# Port.net
KiCad netlist of a schematic drawn in Altium Designer
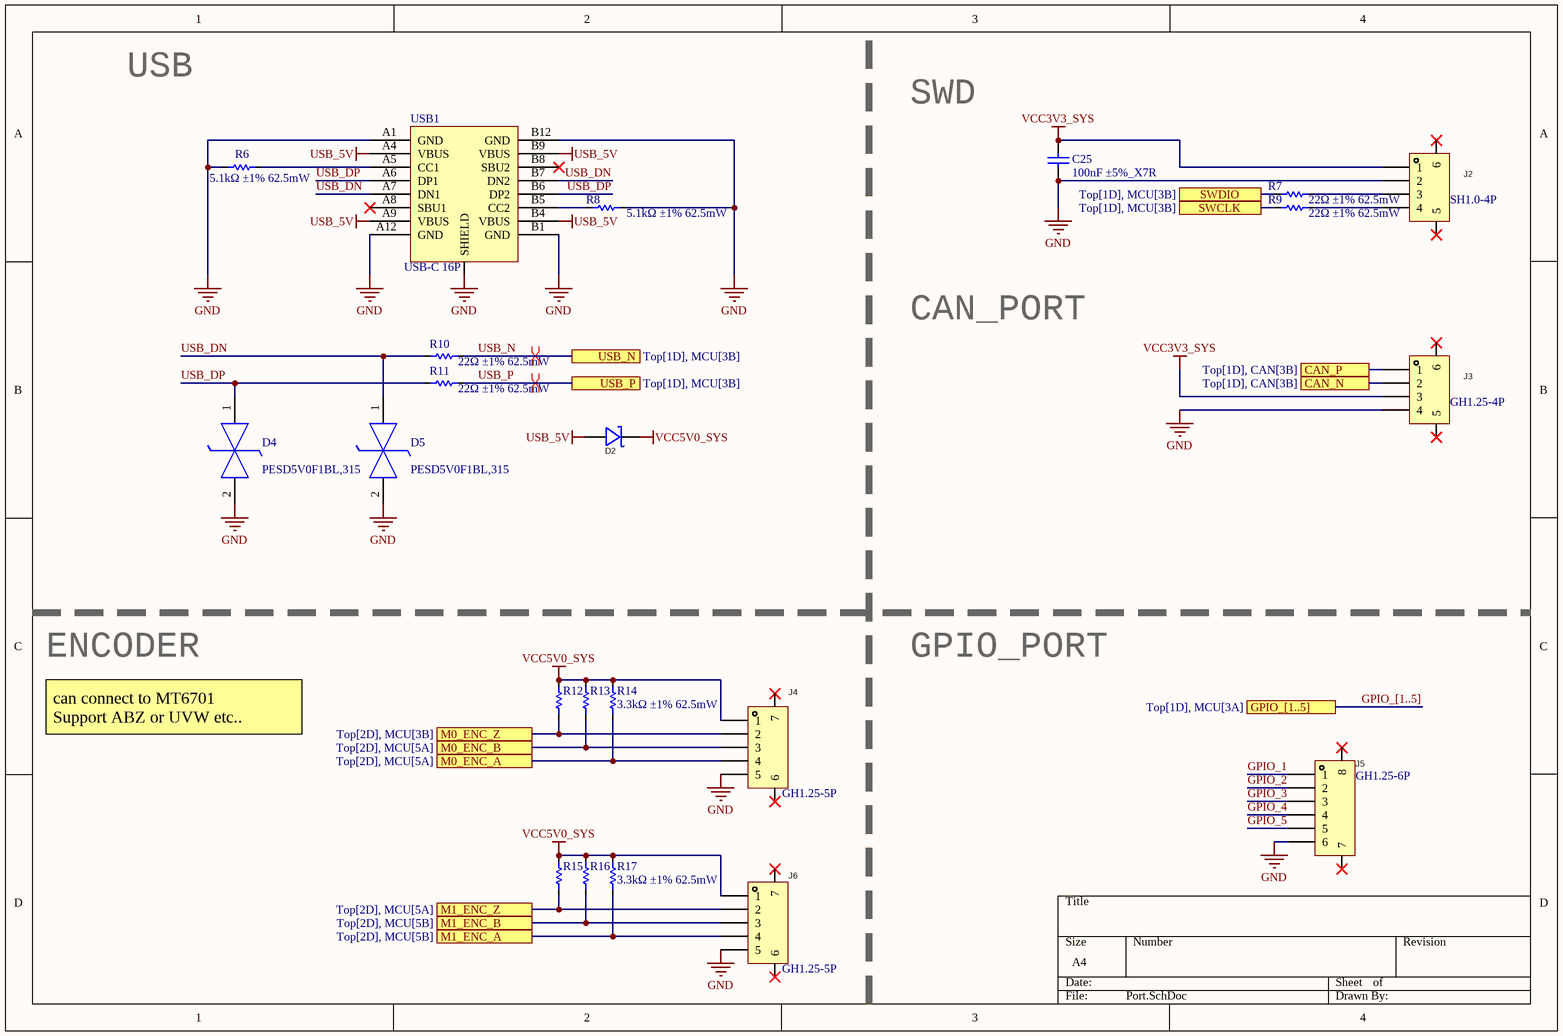
[diagram p0: Port.SchDoc]

(export (version "E")
  (design (tool "Eeschema 10.0.6"))
  (components
    (comp (ref "C25")
      (value "100nF ±5%_X7R")
      (footprint "C0402")
      (description "Capacitor")
      (fields (field (name "PUBLISHER") "Altium Limited"))
      (libsource (lib "Component") (part "Cap"))
    )
    (comp (ref "D2")
      (value "B340A-13-F")
      (footprint "SMA_L4.4-W2.6-LS5.0-RD")
      (description "直流反向耐压(Vr):40V;平均整流电流(Io):3A;正向压降(Vf):500mV@3A;")
      (fields (field (name "MANUFACTURER") "DIODES(美台)"))
      (libsource (lib "Component") (part "Diode_Schottky"))
    )
    (comp (ref "D4")
      (value "PESD5V0F1BL,315")
      (footprint "SamacSys:PESD5V0S1BL315")
      (description "Diode ESD (Bi-directional)")
      (fields (field (name "MOUSER PART NUMBER") "771-PESD5V0F1BL315"))
      (libsource (lib "*") (part "PESD5V0F1BL,315"))
    )
    (comp (ref "D5")
      (value "PESD5V0F1BL,315")
      (footprint "SamacSys:PESD5V0S1BL315")
      (description "Diode ESD (Bi-directional)")
      (fields (field (name "MOUSER PART NUMBER") "771-PESD5V0F1BL315"))
      (libsource (lib "*") (part "PESD5V0F1BL,315"))
    )
    (comp (ref "J2")
      (value "SH1.0-4P")
      (footprint "CONN-SMD_4P-P1.00_BX-SH1.0-4PWT")
      (description "CONN-SMD_4P-P1.25_532610571-2")
      (fields
        (field (name "MANUFACTURER") "BOOMELE(博穆精密)")
        (field (name "MANUFACTURER PART") "GH1.25-5PLTPZ")
      )
      (libsource (lib "Connectivity_Plugs") (part "SH1.0-4P"))
    )
    (comp (ref "J3")
      (value "GH1.25-4P")
      (footprint "GH1.25-4P")
      (fields
        (field (name "MANUFACTURER") "BOOMELE(博穆精密)")
        (field (name "MANUFACTURER PART") "GH1.25-5PLTPZ")
      )
      (libsource (lib "Connectivity_Plugs") (part "GH1.25-4P"))
    )
    (comp (ref "J4")
      (value "GH1.25-5P")
      (footprint "GH1.25-5P")
      (fields
        (field (name "MANUFACTURER") "BOOMELE(博穆精密)")
        (field (name "MANUFACTURER PART") "GH1.25-5PLTPZ")
      )
      (libsource (lib "Connectivity_Plugs") (part "GH1.25-5P"))
    )
    (comp (ref "J5")
      (value "GH1.25-6P")
      (footprint "GH1.25-6P")
      (fields
        (field (name "MANUFACTURER") "BOOMELE(博穆精密)")
        (field (name "MANUFACTURER PART") "GH1.25-5PLTPZ")
      )
      (libsource (lib "Connectivity_Plugs") (part "GH1.25-6P"))
    )
    (comp (ref "J6")
      (value "GH1.25-5P")
      (footprint "GH1.25-5P")
      (fields
        (field (name "MANUFACTURER") "BOOMELE(博穆精密)")
        (field (name "MANUFACTURER PART") "GH1.25-5PLTPZ")
      )
      (libsource (lib "Connectivity_Plugs") (part "GH1.25-5P"))
    )
    (comp (ref "R6")
      (value "5.1kΩ ±1% 62.5mW")
      (footprint "R0402")
      (description "Resistor")
      (fields (field (name "PUBLISHER") "Altium Limited"))
      (libsource (lib "Component") (part "Res"))
    )
    (comp (ref "R7")
      (value "22Ω ±1% 62.5mW")
      (footprint "R0402")
      (description "Resistor")
      (fields (field (name "PUBLISHER") "Altium Limited"))
      (libsource (lib "Component") (part "Res"))
    )
    (comp (ref "R8")
      (value "5.1kΩ ±1% 62.5mW")
      (footprint "R0402")
      (description "Resistor")
      (fields (field (name "PUBLISHER") "Altium Limited"))
      (libsource (lib "Component") (part "Res"))
    )
    (comp (ref "R9")
      (value "22Ω ±1% 62.5mW")
      (footprint "R0402")
      (description "Resistor")
      (fields (field (name "PUBLISHER") "Altium Limited"))
      (libsource (lib "Component") (part "Res"))
    )
    (comp (ref "R10")
      (value "22Ω ±1% 62.5mW")
      (footprint "R0402")
      (description "0402WGF220JTCE")
      (fields (field (name "PUBLISHER") "Altium Limited"))
      (libsource (lib "Component") (part "Res"))
    )
    (comp (ref "R11")
      (value "22Ω ±1% 62.5mW")
      (footprint "R0402")
      (description "0402WGF220JTCE")
      (fields (field (name "PUBLISHER") "Altium Limited"))
      (libsource (lib "Component") (part "Res"))
    )
    (comp (ref "R12")
      (value "3.3kΩ ±1% 62.5mW")
      (footprint "R0402")
      (fields (field (name "PUBLISHER") "Altium Limited"))
      (libsource (lib "Component") (part "Res"))
    )
    (comp (ref "R13")
      (value "3.3kΩ ±1% 62.5mW")
      (footprint "R0402")
      (fields (field (name "PUBLISHER") "Altium Limited"))
      (libsource (lib "Component") (part "Res"))
    )
    (comp (ref "R14")
      (value "3.3kΩ ±1% 62.5mW")
      (footprint "R0402")
      (fields (field (name "PUBLISHER") "Altium Limited"))
      (libsource (lib "Component") (part "Res"))
    )
    (comp (ref "R15")
      (value "3.3kΩ ±1% 62.5mW")
      (footprint "R0402")
      (fields (field (name "PUBLISHER") "Altium Limited"))
      (libsource (lib "Component") (part "Res"))
    )
    (comp (ref "R16")
      (value "3.3kΩ ±1% 62.5mW")
      (footprint "R0402")
      (fields (field (name "PUBLISHER") "Altium Limited"))
      (libsource (lib "Component") (part "Res"))
    )
    (comp (ref "R17")
      (value "3.3kΩ ±1% 62.5mW")
      (footprint "R0402")
      (fields (field (name "PUBLISHER") "Altium Limited"))
      (libsource (lib "Component") (part "Res"))
    )
    (comp (ref "USB1") (value "USB-C 16P") (footprint "USB-C-16P") (libsource (lib "USB") (part "USB-C 16P")))
  )
  (nets
    (net (code "1") (name "/CAN_N") (class "Default")
      (node (ref "J3") (pin "2") (pinfunction "2_2") (pintype "passive"))
    )
    (net (code "2") (name "/CAN_P") (class "Default")
      (node (ref "J3") (pin "1") (pinfunction "1_1") (pintype "passive"))
    )
    (net (code "3") (name "/GPIO_1") (class "Default")
      (node (ref "J5") (pin "1") (pinfunction "1_1") (pintype "passive"))
    )
    (net (code "4") (name "/GPIO_2") (class "Default")
      (node (ref "J5") (pin "2") (pinfunction "2_2") (pintype "passive"))
    )
    (net (code "5") (name "/GPIO_3") (class "Default")
      (node (ref "J5") (pin "3") (pinfunction "3_3") (pintype "passive"))
    )
    (net (code "6") (name "/GPIO_4") (class "Default")
      (node (ref "J5") (pin "4") (pinfunction "4_4") (pintype "passive"))
    )
    (net (code "7") (name "/GPIO_5") (class "Default")
      (node (ref "J5") (pin "5") (pinfunction "5_5") (pintype "passive"))
    )
    (net (code "9") (name "/M0_ENC_A") (class "Default")
      (node (ref "J4") (pin "4") (pinfunction "4_4") (pintype "passive"))
      (node (ref "R14") (pin "1") (pinfunction "1_1") (pintype "passive"))
    )
    (net (code "10") (name "/M0_ENC_B") (class "Default")
      (node (ref "J4") (pin "3") (pinfunction "3_3") (pintype "passive"))
      (node (ref "R13") (pin "1") (pinfunction "1_1") (pintype "passive"))
    )
    (net (code "11") (name "/M0_ENC_Z") (class "Default")
      (node (ref "J4") (pin "2") (pinfunction "2_2") (pintype "passive"))
      (node (ref "R12") (pin "1") (pinfunction "1_1") (pintype "passive"))
    )
    (net (code "12") (name "/M1_ENC_A") (class "Default")
      (node (ref "J6") (pin "4") (pinfunction "4_4") (pintype "passive"))
      (node (ref "R17") (pin "1") (pinfunction "1_1") (pintype "passive"))
    )
    (net (code "13") (name "/M1_ENC_B") (class "Default")
      (node (ref "J6") (pin "3") (pinfunction "3_3") (pintype "passive"))
      (node (ref "R16") (pin "1") (pinfunction "1_1") (pintype "passive"))
    )
    (net (code "14") (name "/M1_ENC_Z") (class "Default")
      (node (ref "J6") (pin "2") (pinfunction "2_2") (pintype "passive"))
      (node (ref "R15") (pin "1") (pinfunction "1_1") (pintype "passive"))
    )
    (net (code "15") (name "/SWCLK") (class "Default")
      (node (ref "R9") (pin "2") (pinfunction "2_2") (pintype "passive"))
    )
    (net (code "16") (name "/SWDIO") (class "Default")
      (node (ref "R7") (pin "1") (pinfunction "1_1") (pintype "passive"))
    )
    (net (code "17") (name "/USB_DN") (class "Default")
      (node (ref "D5") (pin "1") (pinfunction "K1_1") (pintype "passive"))
      (node (ref "R10") (pin "1") (pinfunction "1_1") (pintype "passive"))
      (node (ref "USB1") (pin "A7") (pinfunction "DN1_A7") (pintype "passive"))
      (node (ref "USB1") (pin "B7") (pinfunction "DN2_B7") (pintype "passive"))
    )
    (net (code "18") (name "/USB_DP") (class "Default")
      (node (ref "D4") (pin "1") (pinfunction "K1_1") (pintype "passive"))
      (node (ref "R11") (pin "1") (pinfunction "1_1") (pintype "passive"))
      (node (ref "USB1") (pin "A6") (pinfunction "DP1_A6") (pintype "passive"))
      (node (ref "USB1") (pin "B6") (pinfunction "DP2_B6") (pintype "passive"))
    )
    (net (code "19") (name "/USB_N") (class "Default")
      (node (ref "R10") (pin "2") (pinfunction "2_2") (pintype "passive"))
    )
    (net (code "20") (name "/USB_P") (class "Default")
      (node (ref "R11") (pin "2") (pinfunction "2_2") (pintype "passive"))
    )
    (net (code "21") (name "GND") (class "Default")
      (node (ref "C25") (pin "1") (pinfunction "1_1") (pintype "passive"))
      (node (ref "D4") (pin "2") (pinfunction "K2_2") (pintype "passive"))
      (node (ref "D5") (pin "2") (pinfunction "K2_2") (pintype "passive"))
      (node (ref "J2") (pin "2") (pinfunction "2_2") (pintype "passive"))
      (node (ref "J3") (pin "4") (pinfunction "4_4") (pintype "passive"))
      (node (ref "J4") (pin "5") (pinfunction "5_5") (pintype "passive"))
      (node (ref "J5") (pin "6") (pinfunction "6_6") (pintype "passive"))
      (node (ref "J6") (pin "5") (pinfunction "5_5") (pintype "passive"))
      (node (ref "R6") (pin "1") (pinfunction "1_1") (pintype "passive"))
      (node (ref "R8") (pin "2") (pinfunction "2_2") (pintype "passive"))
      (node (ref "USB1") (pin "0") (pinfunction "SHIELD_0") (pintype "passive"))
      (node (ref "USB1") (pin "A1") (pinfunction "GND_A1") (pintype "passive"))
      (node (ref "USB1") (pin "A12") (pinfunction "GND_A12") (pintype "passive"))
      (node (ref "USB1") (pin "B1") (pinfunction "GND_B1") (pintype "passive"))
      (node (ref "USB1") (pin "B12") (pinfunction "GND_B12") (pintype "passive"))
    )
    (net (code "22") (name "Net-(J2-Pad3)") (class "Default")
      (node (ref "J2") (pin "3") (pinfunction "3_3") (pintype "passive"))
      (node (ref "R7") (pin "2") (pinfunction "2_2") (pintype "passive"))
    )
    (net (code "23") (name "Net-(J2-Pad4)") (class "Default")
      (node (ref "J2") (pin "4") (pinfunction "4_4") (pintype "passive"))
      (node (ref "R9") (pin "1") (pinfunction "1_1") (pintype "passive"))
    )
    (net (code "24") (name "Net-(USB1-CC1)") (class "Default")
      (node (ref "R6") (pin "2") (pinfunction "2_2") (pintype "passive"))
      (node (ref "USB1") (pin "A5") (pinfunction "CC1_A5") (pintype "passive"))
    )
    (net (code "25") (name "Net-(USB1-CC2)") (class "Default")
      (node (ref "R8") (pin "1") (pinfunction "1_1") (pintype "passive"))
      (node (ref "USB1") (pin "B5") (pinfunction "CC2_B5") (pintype "passive"))
    )
    (net (code "26") (name "USB_5V") (class "Default")
      (node (ref "D2") (pin "2") (pinfunction "A_2") (pintype "passive"))
      (node (ref "USB1") (pin "A4") (pinfunction "VBUS_A4") (pintype "passive"))
      (node (ref "USB1") (pin "A9") (pinfunction "VBUS_A9") (pintype "passive"))
      (node (ref "USB1") (pin "B4") (pinfunction "VBUS_B4") (pintype "passive"))
      (node (ref "USB1") (pin "B9") (pinfunction "VBUS_B9") (pintype "passive"))
    )
    (net (code "27") (name "VCC3V3_SYS") (class "Default")
      (node (ref "C25") (pin "2") (pinfunction "2_2") (pintype "passive"))
      (node (ref "J2") (pin "1") (pinfunction "1_1") (pintype "passive"))
      (node (ref "J3") (pin "3") (pinfunction "3_3") (pintype "passive"))
    )
    (net (code "28") (name "VCC5V0_SYS") (class "Default")
      (node (ref "D2") (pin "1") (pinfunction "K_1") (pintype "passive"))
      (node (ref "J4") (pin "1") (pinfunction "1_1") (pintype "passive"))
      (node (ref "J6") (pin "1") (pinfunction "1_1") (pintype "passive"))
      (node (ref "R12") (pin "2") (pinfunction "2_2") (pintype "passive"))
      (node (ref "R13") (pin "2") (pinfunction "2_2") (pintype "passive"))
      (node (ref "R14") (pin "2") (pinfunction "2_2") (pintype "passive"))
      (node (ref "R15") (pin "2") (pinfunction "2_2") (pintype "passive"))
      (node (ref "R16") (pin "2") (pinfunction "2_2") (pintype "passive"))
      (node (ref "R17") (pin "2") (pinfunction "2_2") (pintype "passive"))
    )
    (net (code "29") (name "unconnected-(J2-Pad5)") (class "Default")
      (node (ref "J2") (pin "5") (pinfunction "5_5") (pintype "passive+no_connect"))
    )
    (net (code "30") (name "unconnected-(J2-Pad6)") (class "Default")
      (node (ref "J2") (pin "6") (pinfunction "6_6") (pintype "passive+no_connect"))
    )
    (net (code "31") (name "unconnected-(J3-Pad5)") (class "Default")
      (node (ref "J3") (pin "5") (pinfunction "5_5") (pintype "passive+no_connect"))
    )
    (net (code "32") (name "unconnected-(J3-Pad6)") (class "Default")
      (node (ref "J3") (pin "6") (pinfunction "6_6") (pintype "passive+no_connect"))
    )
    (net (code "33") (name "unconnected-(J4-Pad6)") (class "Default")
      (node (ref "J4") (pin "6") (pinfunction "6_6") (pintype "passive+no_connect"))
    )
    (net (code "34") (name "unconnected-(J4-Pad7)") (class "Default")
      (node (ref "J4") (pin "7") (pinfunction "7_7") (pintype "passive+no_connect"))
    )
    (net (code "35") (name "unconnected-(J5-Pad7)") (class "Default")
      (node (ref "J5") (pin "7") (pinfunction "7_7") (pintype "passive+no_connect"))
    )
    (net (code "36") (name "unconnected-(J5-Pad8)") (class "Default")
      (node (ref "J5") (pin "8") (pinfunction "8_8") (pintype "passive+no_connect"))
    )
    (net (code "37") (name "unconnected-(J6-Pad6)") (class "Default")
      (node (ref "J6") (pin "6") (pinfunction "6_6") (pintype "passive+no_connect"))
    )
    (net (code "38") (name "unconnected-(J6-Pad7)") (class "Default")
      (node (ref "J6") (pin "7") (pinfunction "7_7") (pintype "passive+no_connect"))
    )
    (net (code "39") (name "unconnected-(USB1-SBU1-PadA8)") (class "Default")
      (node (ref "USB1") (pin "A8") (pinfunction "SBU1_A8") (pintype "passive+no_connect"))
    )
    (net (code "40") (name "unconnected-(USB1-SBU2-PadB8)") (class "Default")
      (node (ref "USB1") (pin "B8") (pinfunction "SBU2_B8") (pintype "passive+no_connect"))
    )
  )
)
